# JS7628_base_ethernet_v1_0.net
KiCad netlist of a schematic drawn in Altium Designer
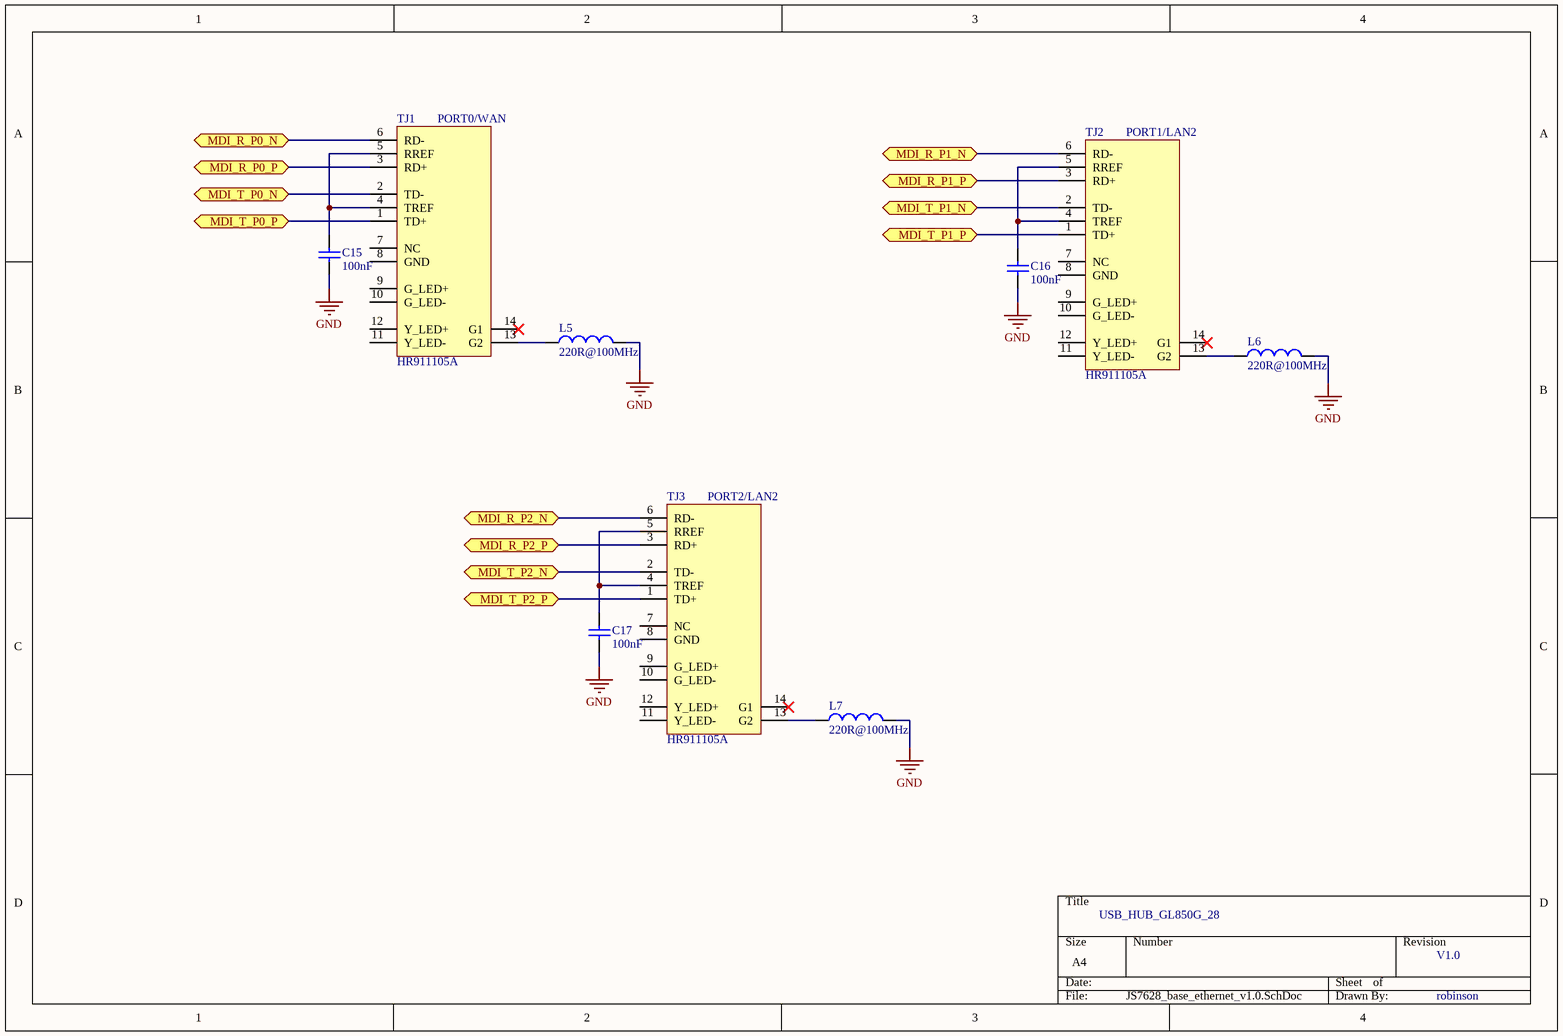
[diagram p0: JS7628_base_ethernet_v1.0.SchDoc]

(export (version "E")
  (design (tool "Eeschema 10.0.6"))
  (components
    (comp (ref "C15")
      (value "100nF")
      (footprint "0603")
      (fields (field (name "Comment") "CAP-SMT"))
      (libsource (lib "MyMiscellaneousDevice") (part "CAP-SMT"))
    )
    (comp (ref "C16")
      (value "100nF")
      (footprint "0603")
      (fields (field (name "Comment") "CAP-SMT"))
      (libsource (lib "MyMiscellaneousDevice") (part "CAP-SMT"))
    )
    (comp (ref "C17")
      (value "100nF")
      (footprint "0603")
      (fields (field (name "Comment") "CAP-SMT"))
      (libsource (lib "MyMiscellaneousDevice") (part "CAP-SMT"))
    )
    (comp (ref "L5")
      (value "220R@100MHz")
      (footprint "0603")
      (fields (field (name "Comment") "inductor"))
      (libsource (lib "MyMiscellaneousDevice") (part "inductor"))
    )
    (comp (ref "L6")
      (value "220R@100MHz")
      (footprint "0603")
      (fields (field (name "Comment") "inductor"))
      (libsource (lib "MyMiscellaneousDevice") (part "inductor"))
    )
    (comp (ref "L7")
      (value "220R@100MHz")
      (footprint "0603")
      (fields (field (name "Comment") "inductor"))
      (libsource (lib "MyMiscellaneousDevice") (part "inductor"))
    )
    (comp (ref "TJ1")
      (value "HR911105A")
      (footprint "HR911105A")
      (fields (field (name "STRING") "PORT0/WAN"))
      (libsource (lib "MyMiscellaneousDevice") (part "HR911105A"))
    )
    (comp (ref "TJ2")
      (value "HR911105A")
      (footprint "HR911105A")
      (fields (field (name "STRING") "PORT1/LAN2"))
      (libsource (lib "MyMiscellaneousDevice") (part "HR911105A"))
    )
    (comp (ref "TJ3")
      (value "HR911105A")
      (footprint "HR911105A")
      (fields (field (name "STRING") "PORT2/LAN2"))
      (libsource (lib "MyMiscellaneousDevice") (part "HR911105A"))
    )
  )
  (nets
    (net (code "1") (name "/MDI_R_P0_N") (class "Default")
      (node (ref "TJ1") (pin "6") (pinfunction "RD-_6") (pintype "passive"))
    )
    (net (code "2") (name "/MDI_R_P0_P") (class "Default")
      (node (ref "TJ1") (pin "3") (pinfunction "RD+_3") (pintype "passive"))
    )
    (net (code "3") (name "/MDI_R_P1_N") (class "Default")
      (node (ref "TJ2") (pin "6") (pinfunction "RD-_6") (pintype "passive"))
    )
    (net (code "4") (name "/MDI_R_P1_P") (class "Default")
      (node (ref "TJ2") (pin "3") (pinfunction "RD+_3") (pintype "passive"))
    )
    (net (code "5") (name "/MDI_R_P2_N") (class "Default")
      (node (ref "TJ3") (pin "6") (pinfunction "RD-_6") (pintype "passive"))
    )
    (net (code "6") (name "/MDI_R_P2_P") (class "Default")
      (node (ref "TJ3") (pin "3") (pinfunction "RD+_3") (pintype "passive"))
    )
    (net (code "7") (name "/MDI_T_P0_N") (class "Default")
      (node (ref "TJ1") (pin "2") (pinfunction "TD-_2") (pintype "passive"))
    )
    (net (code "8") (name "/MDI_T_P0_P") (class "Default")
      (node (ref "TJ1") (pin "1") (pinfunction "TD+_1") (pintype "passive"))
    )
    (net (code "9") (name "/MDI_T_P1_N") (class "Default")
      (node (ref "TJ2") (pin "2") (pinfunction "TD-_2") (pintype "passive"))
    )
    (net (code "10") (name "/MDI_T_P1_P") (class "Default")
      (node (ref "TJ2") (pin "1") (pinfunction "TD+_1") (pintype "passive"))
    )
    (net (code "11") (name "/MDI_T_P2_N") (class "Default")
      (node (ref "TJ3") (pin "2") (pinfunction "TD-_2") (pintype "passive"))
    )
    (net (code "12") (name "/MDI_T_P2_P") (class "Default")
      (node (ref "TJ3") (pin "1") (pinfunction "TD+_1") (pintype "passive"))
    )
    (net (code "13") (name "GND") (class "Default")
      (node (ref "C15") (pin "1") (pinfunction "1_1") (pintype "passive"))
      (node (ref "C16") (pin "1") (pinfunction "1_1") (pintype "passive"))
      (node (ref "C17") (pin "1") (pinfunction "1_1") (pintype "passive"))
      (node (ref "L5") (pin "2") (pinfunction "2_2") (pintype "passive"))
      (node (ref "L6") (pin "2") (pinfunction "2_2") (pintype "passive"))
      (node (ref "L7") (pin "2") (pinfunction "2_2") (pintype "passive"))
    )
    (net (code "14") (name "Net-(TJ1-G2)") (class "Default")
      (node (ref "L5") (pin "1") (pinfunction "1_1") (pintype "passive"))
      (node (ref "TJ1") (pin "13") (pinfunction "G2_13") (pintype "passive"))
    )
    (net (code "15") (name "Net-(TJ1-RREF)") (class "Default")
      (node (ref "C15") (pin "2") (pinfunction "2_2") (pintype "passive"))
      (node (ref "TJ1") (pin "4") (pinfunction "TREF_4") (pintype "passive"))
      (node (ref "TJ1") (pin "5") (pinfunction "RREF_5") (pintype "passive"))
    )
    (net (code "16") (name "Net-(TJ2-G2)") (class "Default")
      (node (ref "L6") (pin "1") (pinfunction "1_1") (pintype "passive"))
      (node (ref "TJ2") (pin "13") (pinfunction "G2_13") (pintype "passive"))
    )
    (net (code "17") (name "Net-(TJ2-RREF)") (class "Default")
      (node (ref "C16") (pin "2") (pinfunction "2_2") (pintype "passive"))
      (node (ref "TJ2") (pin "4") (pinfunction "TREF_4") (pintype "passive"))
      (node (ref "TJ2") (pin "5") (pinfunction "RREF_5") (pintype "passive"))
    )
    (net (code "18") (name "Net-(TJ3-G2)") (class "Default")
      (node (ref "L7") (pin "1") (pinfunction "1_1") (pintype "passive"))
      (node (ref "TJ3") (pin "13") (pinfunction "G2_13") (pintype "passive"))
    )
    (net (code "19") (name "Net-(TJ3-RREF)") (class "Default")
      (node (ref "C17") (pin "2") (pinfunction "2_2") (pintype "passive"))
      (node (ref "TJ3") (pin "4") (pinfunction "TREF_4") (pintype "passive"))
      (node (ref "TJ3") (pin "5") (pinfunction "RREF_5") (pintype "passive"))
    )
    (net (code "20") (name "unconnected-(TJ1-G1-Pad14)") (class "Default")
      (node (ref "TJ1") (pin "14") (pinfunction "G1_14") (pintype "passive+no_connect"))
    )
    (net (code "21") (name "unconnected-(TJ1-GND-Pad8)") (class "Default")
      (node (ref "TJ1") (pin "8") (pinfunction "GND_8") (pintype "passive"))
    )
    (net (code "22") (name "unconnected-(TJ1-G_LED+-Pad9)") (class "Default")
      (node (ref "TJ1") (pin "9") (pinfunction "G_LED+_9") (pintype "passive"))
    )
    (net (code "23") (name "unconnected-(TJ1-G_LED--Pad10)") (class "Default")
      (node (ref "TJ1") (pin "10") (pinfunction "G_LED-_10") (pintype "passive"))
    )
    (net (code "24") (name "unconnected-(TJ1-NC-Pad7)") (class "Default")
      (node (ref "TJ1") (pin "7") (pinfunction "NC_7") (pintype "passive"))
    )
    (net (code "25") (name "unconnected-(TJ1-Y_LED+-Pad12)") (class "Default")
      (node (ref "TJ1") (pin "12") (pinfunction "Y_LED+_12") (pintype "passive"))
    )
    (net (code "26") (name "unconnected-(TJ1-Y_LED--Pad11)") (class "Default")
      (node (ref "TJ1") (pin "11") (pinfunction "Y_LED-_11") (pintype "passive"))
    )
    (net (code "27") (name "unconnected-(TJ2-G1-Pad14)") (class "Default")
      (node (ref "TJ2") (pin "14") (pinfunction "G1_14") (pintype "passive+no_connect"))
    )
    (net (code "28") (name "unconnected-(TJ2-GND-Pad8)") (class "Default")
      (node (ref "TJ2") (pin "8") (pinfunction "GND_8") (pintype "passive"))
    )
    (net (code "29") (name "unconnected-(TJ2-G_LED+-Pad9)") (class "Default")
      (node (ref "TJ2") (pin "9") (pinfunction "G_LED+_9") (pintype "passive"))
    )
    (net (code "30") (name "unconnected-(TJ2-G_LED--Pad10)") (class "Default")
      (node (ref "TJ2") (pin "10") (pinfunction "G_LED-_10") (pintype "passive"))
    )
    (net (code "31") (name "unconnected-(TJ2-NC-Pad7)") (class "Default")
      (node (ref "TJ2") (pin "7") (pinfunction "NC_7") (pintype "passive"))
    )
    (net (code "32") (name "unconnected-(TJ2-Y_LED+-Pad12)") (class "Default")
      (node (ref "TJ2") (pin "12") (pinfunction "Y_LED+_12") (pintype "passive"))
    )
    (net (code "33") (name "unconnected-(TJ2-Y_LED--Pad11)") (class "Default")
      (node (ref "TJ2") (pin "11") (pinfunction "Y_LED-_11") (pintype "passive"))
    )
    (net (code "34") (name "unconnected-(TJ3-G1-Pad14)") (class "Default")
      (node (ref "TJ3") (pin "14") (pinfunction "G1_14") (pintype "passive+no_connect"))
    )
    (net (code "35") (name "unconnected-(TJ3-GND-Pad8)") (class "Default")
      (node (ref "TJ3") (pin "8") (pinfunction "GND_8") (pintype "passive"))
    )
    (net (code "36") (name "unconnected-(TJ3-G_LED+-Pad9)") (class "Default")
      (node (ref "TJ3") (pin "9") (pinfunction "G_LED+_9") (pintype "passive"))
    )
    (net (code "37") (name "unconnected-(TJ3-G_LED--Pad10)") (class "Default")
      (node (ref "TJ3") (pin "10") (pinfunction "G_LED-_10") (pintype "passive"))
    )
    (net (code "38") (name "unconnected-(TJ3-NC-Pad7)") (class "Default")
      (node (ref "TJ3") (pin "7") (pinfunction "NC_7") (pintype "passive"))
    )
    (net (code "39") (name "unconnected-(TJ3-Y_LED+-Pad12)") (class "Default")
      (node (ref "TJ3") (pin "12") (pinfunction "Y_LED+_12") (pintype "passive"))
    )
    (net (code "40") (name "unconnected-(TJ3-Y_LED--Pad11)") (class "Default")
      (node (ref "TJ3") (pin "11") (pinfunction "Y_LED-_11") (pintype "passive"))
    )
  )
)
